# MySensors_AirQuality_Board_2017-11-27_es.net
KiCad netlist of a schematic drawn in EAGLE
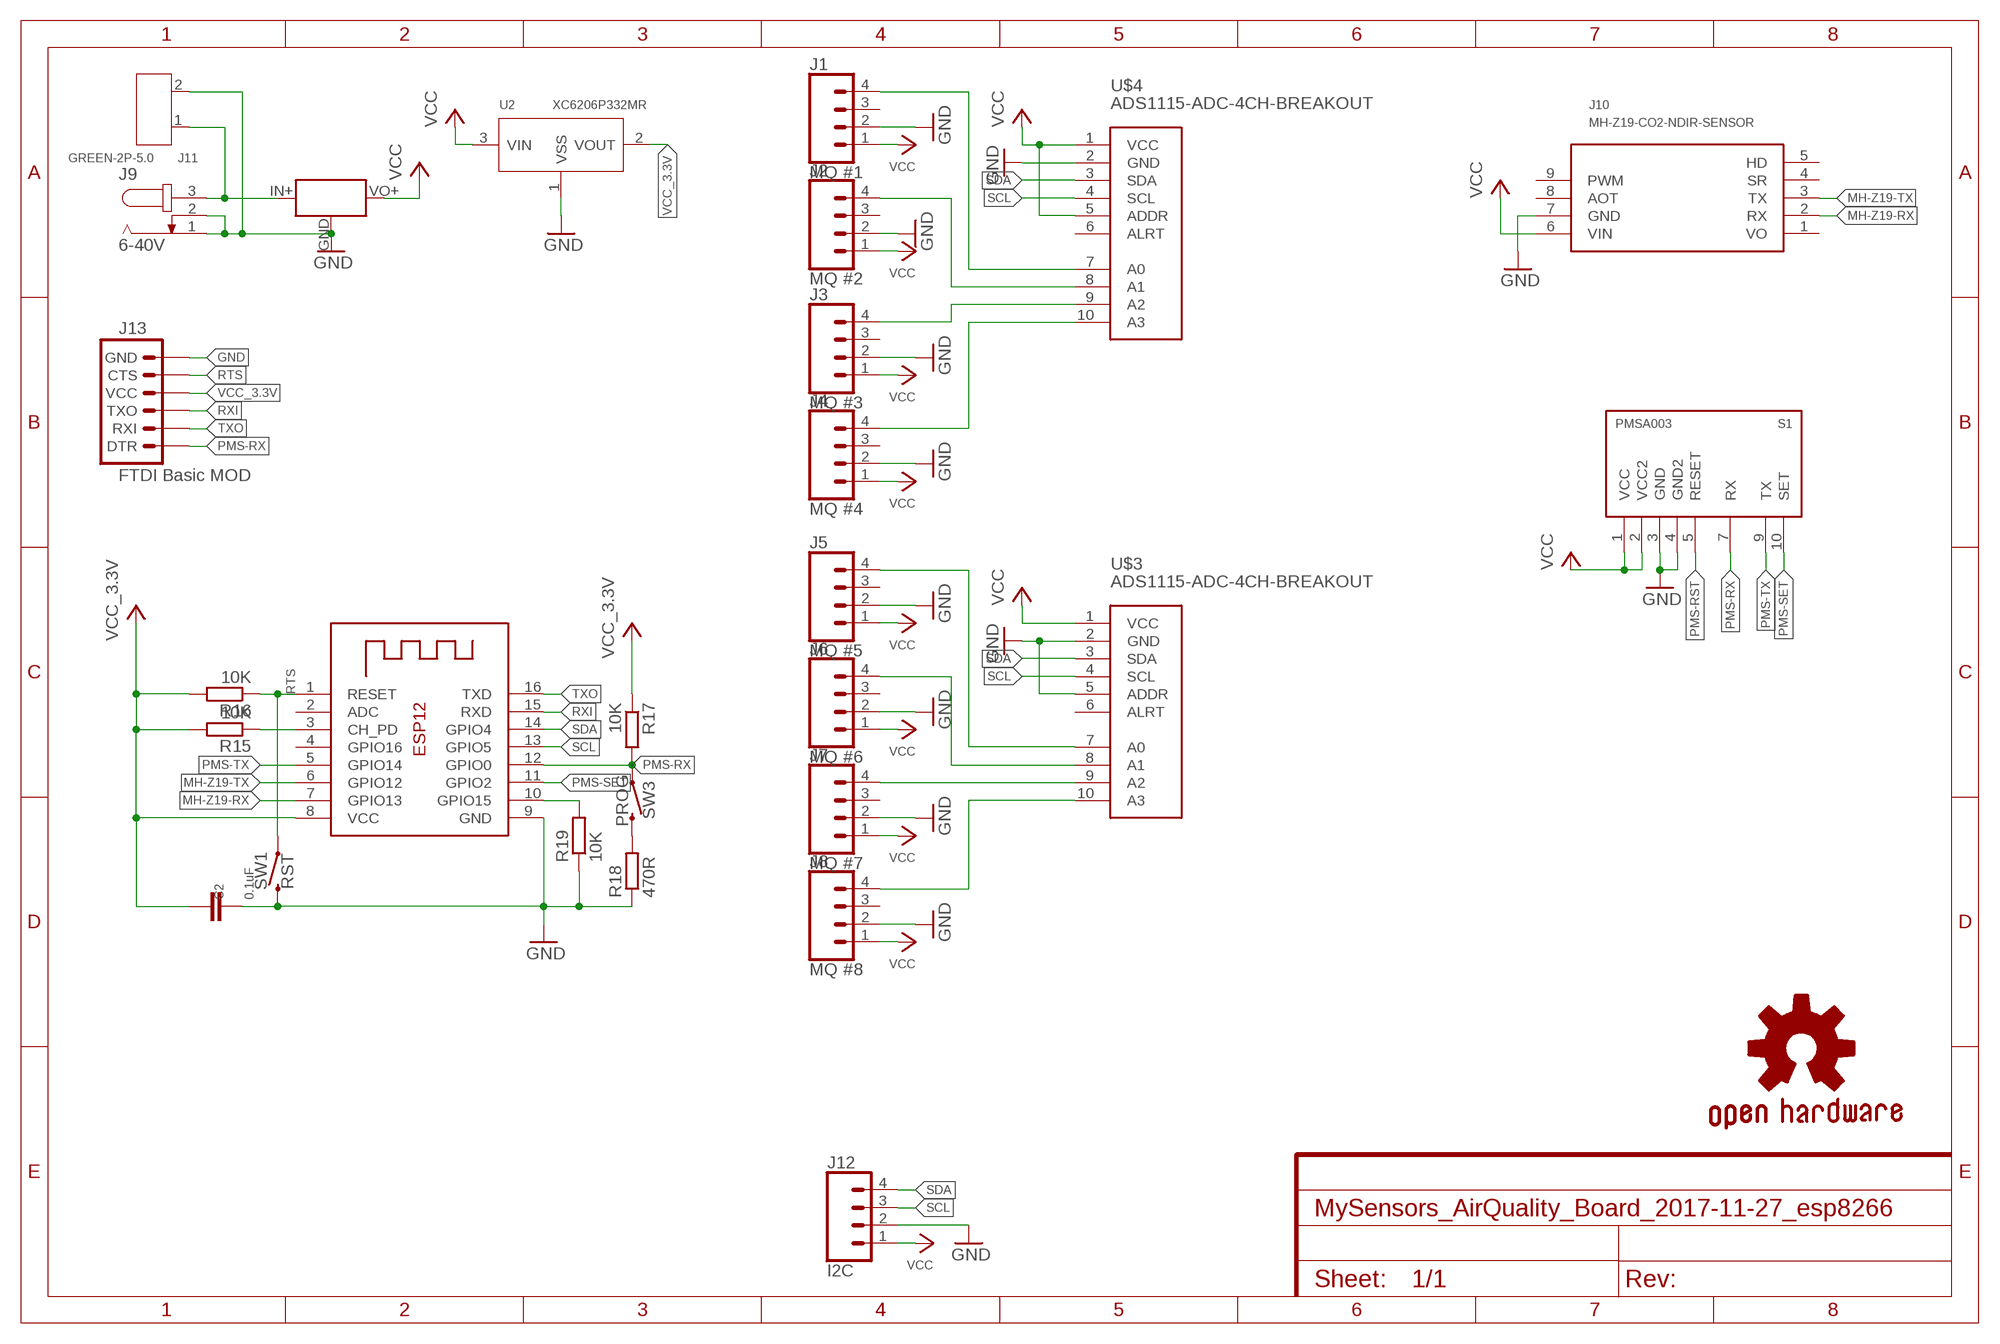
[diagram p0: schematic, sheet 1]

(export (version "E")
  (design (tool "Eeschema 10.0.6"))
  (components
    (comp (ref "C2")
      (value "0.1uF")
      (footprint "eagle-import:C0805")
      (libsource (lib "eagle-import") (part "C-EUC0805"))
    )
    (comp (ref "GOLD_ORB_SM1")
      (value "OSHWLOGO_GOLD_ORB_SM")
      (footprint "eagle-import:OSHW2")
      (libsource (lib "eagle-import") (part "OSHWLOGO_GOLD_ORB_SM"))
    )
    (comp (ref "J1")
      (value "MQ #1")
      (footprint "eagle-import:1X04")
      (libsource (lib "eagle-import") (part "CONN_04"))
    )
    (comp (ref "J2")
      (value "MQ #2")
      (footprint "eagle-import:1X04")
      (libsource (lib "eagle-import") (part "CONN_04"))
    )
    (comp (ref "J3")
      (value "MQ #3")
      (footprint "eagle-import:1X04")
      (libsource (lib "eagle-import") (part "CONN_04"))
    )
    (comp (ref "J4")
      (value "MQ #4")
      (footprint "eagle-import:1X04")
      (libsource (lib "eagle-import") (part "CONN_04"))
    )
    (comp (ref "J5")
      (value "MQ #5")
      (footprint "eagle-import:1X04")
      (libsource (lib "eagle-import") (part "CONN_04"))
    )
    (comp (ref "J6")
      (value "MQ #6")
      (footprint "eagle-import:1X04")
      (libsource (lib "eagle-import") (part "CONN_04"))
    )
    (comp (ref "J7")
      (value "MQ #7")
      (footprint "eagle-import:1X04")
      (libsource (lib "eagle-import") (part "CONN_04"))
    )
    (comp (ref "J8")
      (value "MQ #8")
      (footprint "eagle-import:1X04")
      (libsource (lib "eagle-import") (part "CONN_04"))
    )
    (comp (ref "J9")
      (value "6-40V")
      (footprint "eagle-import:SPC4078")
      (libsource (lib "eagle-import") (part "JACK-PLUG1"))
    )
    (comp (ref "J10")
      (value "MH-Z19-CO2-NDIR-SENSOR")
      (footprint "eagle-import:MH-Z19")
      (libsource (lib "eagle-import") (part "MH-Z19-CO2-NDIR-SENSOR"))
    )
    (comp (ref "J11")
      (value "GREEN-2P-5.0")
      (footprint "eagle-import:H2-5.0-10.5X8.0MM")
      (libsource (lib "eagle-import") (part "SCREW-TERMINAL-GREEN(2P-5.0)"))
    )
    (comp (ref "J12")
      (value "I2C")
      (footprint "eagle-import:1X04")
      (libsource (lib "eagle-import") (part "CONN_04"))
    )
    (comp (ref "J13")
      (value "FTDI Basic MOD")
      (footprint "eagle-import:1X06")
      (libsource (lib "eagle-import") (part "ARDUINO_SERIAL_PROGRAMPTH"))
    )
    (comp (ref "R15")
      (value "10K")
      (footprint "eagle-import:R0805")
      (libsource (lib "eagle-import") (part "R-EU_R0805"))
    )
    (comp (ref "R16")
      (value "10K")
      (footprint "eagle-import:R0805")
      (libsource (lib "eagle-import") (part "R-EU_R0805"))
    )
    (comp (ref "R17")
      (value "10K")
      (footprint "eagle-import:R0805")
      (libsource (lib "eagle-import") (part "R-EU_R0805"))
    )
    (comp (ref "R18")
      (value "470R")
      (footprint "eagle-import:R0805")
      (libsource (lib "eagle-import") (part "R-EU_R0805"))
    )
    (comp (ref "R19")
      (value "10K")
      (footprint "eagle-import:R0805")
      (libsource (lib "eagle-import") (part "R-EU_R0805"))
    )
    (comp (ref "S1")
      (value "PMSA003")
      (footprint "eagle-import:PMSA003")
      (libsource (lib "eagle-import") (part "PMSA003"))
    )
    (comp (ref "SW1")
      (value "RST")
      (footprint "eagle-import:TACTILE_SWITCH_SMD_6.0X3.5MM")
      (libsource (lib "eagle-import") (part "MOMENTARY-SWITCH-SPST-SMD-6.0X3.5MM"))
    )
    (comp (ref "SW3")
      (value "PROG")
      (footprint "eagle-import:TACTILE_SWITCH_SMD_6.0X3.5MM")
      (libsource (lib "eagle-import") (part "MOMENTARY-SWITCH-SPST-SMD-6.0X3.5MM"))
    )
    (comp (ref "U$2")
      (value "MINI_BUCK_CONVERTER")
      (footprint "eagle-import:MINI_BUCK_CONVERTER")
      (libsource (lib "eagle-import") (part "MINI_BUCK_CONVERTER"))
    )
    (comp (ref "U$3")
      (value "ADS1115-ADC-4CH-BREAKOUT")
      (footprint "eagle-import:ADS1115-ADC-4CH-BREAKOUT")
      (libsource (lib "eagle-import") (part "ADS1115-ADC-4CH-BREAKOUT"))
    )
    (comp (ref "U$4")
      (value "ADS1115-ADC-4CH-BREAKOUT")
      (footprint "eagle-import:ADS1115-ADC-4CH-BREAKOUT")
      (libsource (lib "eagle-import") (part "ADS1115-ADC-4CH-BREAKOUT"))
    )
    (comp (ref "U2")
      (value "XC6206P332MR")
      (footprint "eagle-import:SOT-23")
      (fields (field (name "MPN") "XC6206P332MR-G"))
      (libsource (lib "eagle-import") (part "PMIC-LDO-XC6206P332MR-G(SOT23)"))
    )
    (comp (ref "X2")
      (value "ESP-12e")
      (footprint "eagle-import:ESP-12")
      (libsource (lib "eagle-import") (part "ESP-12"))
    )
  )
  (nets
    (net (code "1") (name "/VO") (class "Default")
      (node (ref "J10") (pin "1") (pinfunction "VO_1") (pintype "power_in"))
    )
    (net (code "2") (name "GND") (class "Default")
      (node (ref "C2") (pin "1") (pinfunction "1_1") (pintype "passive"))
      (node (ref "J1") (pin "2") (pinfunction "2_2") (pintype "passive"))
      (node (ref "J10") (pin "7") (pinfunction "GND_7") (pintype "power_in"))
      (node (ref "J11") (pin "2") (pinfunction "2_2") (pintype "bidirectional"))
      (node (ref "J12") (pin "2") (pinfunction "2_2") (pintype "passive"))
      (node (ref "J13") (pin "6") (pinfunction "GND_6") (pintype "passive"))
      (node (ref "J2") (pin "2") (pinfunction "2_2") (pintype "passive"))
      (node (ref "J3") (pin "2") (pinfunction "2_2") (pintype "passive"))
      (node (ref "J4") (pin "2") (pinfunction "2_2") (pintype "passive"))
      (node (ref "J5") (pin "2") (pinfunction "2_2") (pintype "passive"))
      (node (ref "J6") (pin "2") (pinfunction "2_2") (pintype "passive"))
      (node (ref "J7") (pin "2") (pinfunction "2_2") (pintype "passive"))
      (node (ref "J8") (pin "2") (pinfunction "2_2") (pintype "passive"))
      (node (ref "J9") (pin "1") (pinfunction "1_1") (pintype "passive"))
      (node (ref "J9") (pin "2") (pinfunction "2_2") (pintype "passive"))
      (node (ref "R18") (pin "1") (pinfunction "1_1") (pintype "passive"))
      (node (ref "R19") (pin "1") (pinfunction "1_1") (pintype "passive"))
      (node (ref "S1") (pin "3") (pinfunction "GND_3") (pintype "bidirectional"))
      (node (ref "S1") (pin "4") (pinfunction "GND2_4") (pintype "bidirectional"))
      (node (ref "SW1") (pin "2") (pinfunction "2_2") (pintype "passive"))
      (node (ref "U$2") (pin "GND") (pinfunction "GND_GND") (pintype "bidirectional"))
      (node (ref "U$3") (pin "2") (pinfunction "GND_2") (pintype "power_in"))
      (node (ref "U$3") (pin "5") (pinfunction "ADDR_5") (pintype "bidirectional"))
      (node (ref "U$4") (pin "2") (pinfunction "GND_2") (pintype "power_in"))
      (node (ref "U2") (pin "1") (pinfunction "VSS_1") (pintype "power_in"))
      (node (ref "X2") (pin "9") (pinfunction "GND_9") (pintype "power_in"))
    )
    (net (code "3") (name "MH-Z19-RX") (class "Default")
      (node (ref "J10") (pin "2") (pinfunction "RX_2") (pintype "input"))
      (node (ref "X2") (pin "7") (pinfunction "GPIO13_7") (pintype "bidirectional"))
    )
    (net (code "4") (name "MH-Z19-TX") (class "Default")
      (node (ref "J10") (pin "3") (pinfunction "TX_3") (pintype "output"))
      (node (ref "X2") (pin "6") (pinfunction "GPIO12_6") (pintype "bidirectional"))
    )
    (net (code "5") (name "Net-(R18-Pad2)") (class "Default")
      (node (ref "R18") (pin "2") (pinfunction "2_2") (pintype "passive"))
      (node (ref "SW3") (pin "2") (pinfunction "2_2") (pintype "passive"))
    )
    (net (code "6") (name "Net-(U$2-VIN)") (class "Default")
      (node (ref "J11") (pin "1") (pinfunction "1_1") (pintype "bidirectional"))
      (node (ref "J9") (pin "3") (pinfunction "3_3") (pintype "passive"))
      (node (ref "U$2") (pin "IN+") (pinfunction "VIN_IN+") (pintype "input"))
    )
    (net (code "7") (name "Net-(U$3-A0)") (class "Default")
      (node (ref "J5") (pin "4") (pinfunction "4_4") (pintype "passive"))
      (node (ref "U$3") (pin "7") (pinfunction "A0_7") (pintype "input"))
    )
    (net (code "8") (name "Net-(U$3-A1)") (class "Default")
      (node (ref "J6") (pin "4") (pinfunction "4_4") (pintype "passive"))
      (node (ref "U$3") (pin "8") (pinfunction "A1_8") (pintype "input"))
    )
    (net (code "9") (name "Net-(U$3-A2)") (class "Default")
      (node (ref "J7") (pin "4") (pinfunction "4_4") (pintype "passive"))
      (node (ref "U$3") (pin "9") (pinfunction "A2_9") (pintype "input"))
    )
    (net (code "10") (name "Net-(U$3-A3)") (class "Default")
      (node (ref "J8") (pin "4") (pinfunction "4_4") (pintype "passive"))
      (node (ref "U$3") (pin "10") (pinfunction "A3_10") (pintype "input"))
    )
    (net (code "11") (name "Net-(U$4-A0)") (class "Default")
      (node (ref "J1") (pin "4") (pinfunction "4_4") (pintype "passive"))
      (node (ref "U$4") (pin "7") (pinfunction "A0_7") (pintype "input"))
    )
    (net (code "12") (name "Net-(U$4-A1)") (class "Default")
      (node (ref "J2") (pin "4") (pinfunction "4_4") (pintype "passive"))
      (node (ref "U$4") (pin "8") (pinfunction "A1_8") (pintype "input"))
    )
    (net (code "13") (name "Net-(U$4-A2)") (class "Default")
      (node (ref "J3") (pin "4") (pinfunction "4_4") (pintype "passive"))
      (node (ref "U$4") (pin "9") (pinfunction "A2_9") (pintype "input"))
    )
    (net (code "14") (name "Net-(U$4-A3)") (class "Default")
      (node (ref "J4") (pin "4") (pinfunction "4_4") (pintype "passive"))
      (node (ref "U$4") (pin "10") (pinfunction "A3_10") (pintype "input"))
    )
    (net (code "15") (name "Net-(X2-CH_PD)") (class "Default")
      (node (ref "R15") (pin "1") (pinfunction "1_1") (pintype "passive"))
      (node (ref "X2") (pin "3") (pinfunction "CH_PD_3") (pintype "input"))
    )
    (net (code "16") (name "Net-(X2-GPIO15)") (class "Default")
      (node (ref "R19") (pin "2") (pinfunction "2_2") (pintype "passive"))
      (node (ref "X2") (pin "10") (pinfunction "GPIO15_10") (pintype "bidirectional"))
    )
    (net (code "17") (name "PMS-RST") (class "Default")
      (node (ref "S1") (pin "5") (pinfunction "RESET_5") (pintype "bidirectional"))
    )
    (net (code "18") (name "PMS-RX") (class "Default")
      (node (ref "J13") (pin "1") (pinfunction "DTR_1") (pintype "passive"))
      (node (ref "R17") (pin "2") (pinfunction "2_2") (pintype "passive"))
      (node (ref "S1") (pin "7") (pinfunction "RX_7") (pintype "bidirectional"))
      (node (ref "SW3") (pin "1") (pinfunction "1_1") (pintype "passive"))
      (node (ref "X2") (pin "12") (pinfunction "GPIO0_12") (pintype "bidirectional"))
    )
    (net (code "19") (name "PMS-SET") (class "Default")
      (node (ref "S1") (pin "10") (pinfunction "SET_10") (pintype "bidirectional"))
      (node (ref "X2") (pin "11") (pinfunction "GPIO2_11") (pintype "bidirectional"))
    )
    (net (code "20") (name "PMS-TX") (class "Default")
      (node (ref "S1") (pin "9") (pinfunction "TX_9") (pintype "bidirectional"))
      (node (ref "X2") (pin "5") (pinfunction "GPIO14_5") (pintype "bidirectional"))
    )
    (net (code "21") (name "RTS") (class "Default")
      (node (ref "J13") (pin "5") (pinfunction "CTS_5") (pintype "passive"))
      (node (ref "R16") (pin "1") (pinfunction "1_1") (pintype "passive"))
      (node (ref "SW1") (pin "1") (pinfunction "1_1") (pintype "passive"))
      (node (ref "X2") (pin "1") (pinfunction "RESET_1") (pintype "input"))
    )
    (net (code "22") (name "RXI") (class "Default")
      (node (ref "J13") (pin "3") (pinfunction "TXO_3") (pintype "passive"))
      (node (ref "X2") (pin "15") (pinfunction "RXD_15") (pintype "input"))
    )
    (net (code "23") (name "SCL") (class "Default")
      (node (ref "J12") (pin "3") (pinfunction "3_3") (pintype "passive"))
      (node (ref "U$3") (pin "4") (pinfunction "SCL_4") (pintype "bidirectional"))
      (node (ref "U$4") (pin "4") (pinfunction "SCL_4") (pintype "bidirectional"))
      (node (ref "X2") (pin "13") (pinfunction "GPIO5_13") (pintype "bidirectional"))
    )
    (net (code "24") (name "SDA") (class "Default")
      (node (ref "J12") (pin "4") (pinfunction "4_4") (pintype "passive"))
      (node (ref "U$3") (pin "3") (pinfunction "SDA_3") (pintype "bidirectional"))
      (node (ref "U$4") (pin "3") (pinfunction "SDA_3") (pintype "bidirectional"))
      (node (ref "X2") (pin "14") (pinfunction "GPIO4_14") (pintype "bidirectional"))
    )
    (net (code "25") (name "TXO") (class "Default")
      (node (ref "J13") (pin "2") (pinfunction "RXI_2") (pintype "passive"))
      (node (ref "X2") (pin "16") (pinfunction "TXD_16") (pintype "output"))
    )
    (net (code "26") (name "VCC") (class "Default")
      (node (ref "J1") (pin "1") (pinfunction "1_1") (pintype "passive"))
      (node (ref "J10") (pin "6") (pinfunction "VIN_6") (pintype "power_in"))
      (node (ref "J12") (pin "1") (pinfunction "1_1") (pintype "passive"))
      (node (ref "J2") (pin "1") (pinfunction "1_1") (pintype "passive"))
      (node (ref "J3") (pin "1") (pinfunction "1_1") (pintype "passive"))
      (node (ref "J4") (pin "1") (pinfunction "1_1") (pintype "passive"))
      (node (ref "J5") (pin "1") (pinfunction "1_1") (pintype "passive"))
      (node (ref "J6") (pin "1") (pinfunction "1_1") (pintype "passive"))
      (node (ref "J7") (pin "1") (pinfunction "1_1") (pintype "passive"))
      (node (ref "J8") (pin "1") (pinfunction "1_1") (pintype "passive"))
      (node (ref "S1") (pin "1") (pinfunction "VCC_1") (pintype "bidirectional"))
      (node (ref "S1") (pin "2") (pinfunction "VCC2_2") (pintype "bidirectional"))
      (node (ref "U$2") (pin "VO+") (pinfunction "VOUT_VO+") (pintype "power_in"))
      (node (ref "U$3") (pin "1") (pinfunction "VCC_1") (pintype "power_in"))
      (node (ref "U$4") (pin "1") (pinfunction "VCC_1") (pintype "power_in"))
      (node (ref "U$4") (pin "5") (pinfunction "ADDR_5") (pintype "bidirectional"))
      (node (ref "U2") (pin "3") (pinfunction "VIN_3") (pintype "input"))
    )
    (net (code "27") (name "VCC_3.3V") (class "Default")
      (node (ref "C2") (pin "2") (pinfunction "2_2") (pintype "passive"))
      (node (ref "J13") (pin "4") (pinfunction "VCC_4") (pintype "passive"))
      (node (ref "R15") (pin "2") (pinfunction "2_2") (pintype "passive"))
      (node (ref "R16") (pin "2") (pinfunction "2_2") (pintype "passive"))
      (node (ref "R17") (pin "1") (pinfunction "1_1") (pintype "passive"))
      (node (ref "U2") (pin "2") (pinfunction "VOUT_2") (pintype "output"))
      (node (ref "X2") (pin "8") (pinfunction "VCC_8") (pintype "power_in"))
    )
    (net (code "28") (name "unconnected-(J1-Pad3)") (class "Default")
      (node (ref "J1") (pin "3") (pinfunction "3_3") (pintype "passive"))
    )
    (net (code "29") (name "unconnected-(J2-Pad3)") (class "Default")
      (node (ref "J2") (pin "3") (pinfunction "3_3") (pintype "passive"))
    )
    (net (code "30") (name "unconnected-(J3-Pad3)") (class "Default")
      (node (ref "J3") (pin "3") (pinfunction "3_3") (pintype "passive"))
    )
    (net (code "31") (name "unconnected-(J4-Pad3)") (class "Default")
      (node (ref "J4") (pin "3") (pinfunction "3_3") (pintype "passive"))
    )
    (net (code "32") (name "unconnected-(J5-Pad3)") (class "Default")
      (node (ref "J5") (pin "3") (pinfunction "3_3") (pintype "passive"))
    )
    (net (code "33") (name "unconnected-(J6-Pad3)") (class "Default")
      (node (ref "J6") (pin "3") (pinfunction "3_3") (pintype "passive"))
    )
    (net (code "34") (name "unconnected-(J7-Pad3)") (class "Default")
      (node (ref "J7") (pin "3") (pinfunction "3_3") (pintype "passive"))
    )
    (net (code "35") (name "unconnected-(J8-Pad3)") (class "Default")
      (node (ref "J8") (pin "3") (pinfunction "3_3") (pintype "passive"))
    )
    (net (code "36") (name "unconnected-(J10-AOT-Pad8)") (class "Default")
      (node (ref "J10") (pin "8") (pinfunction "AOT_8") (pintype "no_connect"))
    )
    (net (code "37") (name "unconnected-(J10-HD-Pad5)") (class "Default")
      (node (ref "J10") (pin "5") (pinfunction "HD_5") (pintype "input"))
    )
    (net (code "38") (name "unconnected-(J10-PWM-Pad9)") (class "Default")
      (node (ref "J10") (pin "9") (pinfunction "PWM_9") (pintype "output"))
    )
    (net (code "39") (name "unconnected-(J10-SR-Pad4)") (class "Default")
      (node (ref "J10") (pin "4") (pinfunction "SR_4") (pintype "no_connect"))
    )
    (net (code "40") (name "unconnected-(U$3-ALRT-Pad6)") (class "Default")
      (node (ref "U$3") (pin "6") (pinfunction "ALRT_6") (pintype "bidirectional"))
    )
    (net (code "41") (name "unconnected-(U$4-ALRT-Pad6)") (class "Default")
      (node (ref "U$4") (pin "6") (pinfunction "ALRT_6") (pintype "bidirectional"))
    )
    (net (code "42") (name "unconnected-(X2-ADC-Pad2)") (class "Default")
      (node (ref "X2") (pin "2") (pinfunction "ADC_2") (pintype "passive"))
    )
    (net (code "43") (name "unconnected-(X2-GPIO16-Pad4)") (class "Default")
      (node (ref "X2") (pin "4") (pinfunction "GPIO16_4") (pintype "bidirectional"))
    )
  )
)
